# sub.net
KiCad netlist of a schematic drawn in EAGLE
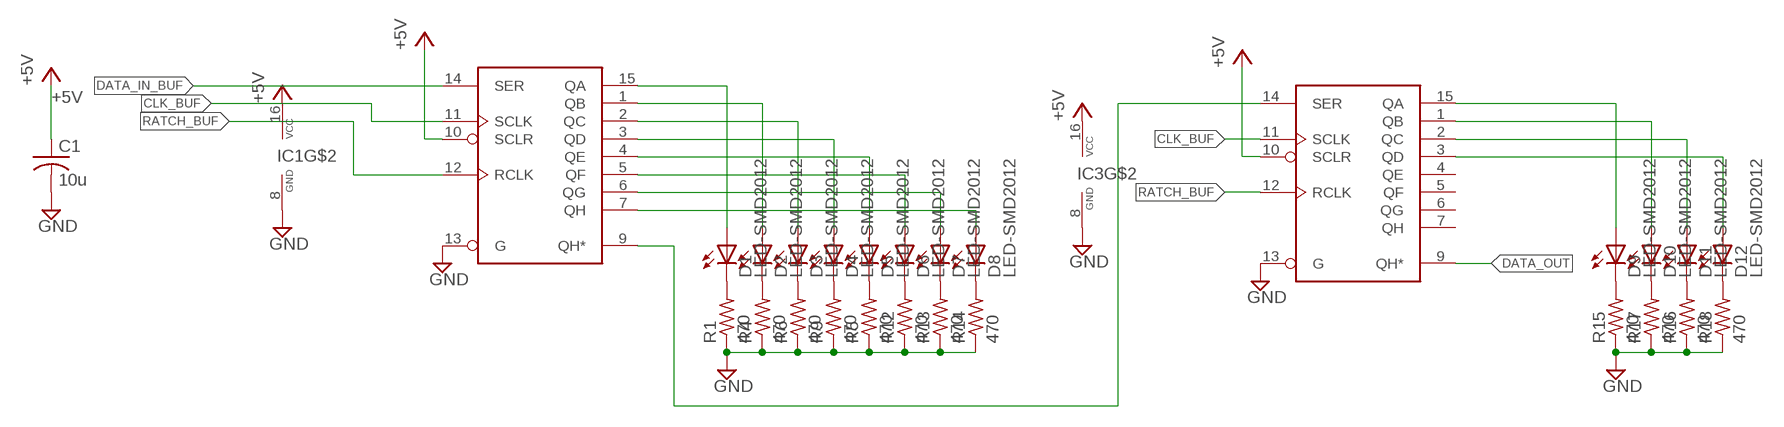
[diagram p0: schematic, sheet 1]

(export (version "E")
  (design (tool "Eeschema 10.0.6"))
  (components
    (comp (ref "C1")
      (value "10u")
      (footprint "eagle-import:2012-C")
      (libsource (lib "eagle-import") (part "C-2012"))
    )
    (comp (ref "D1")
      (value "LED-SMD2012")
      (footprint "eagle-import:D2012")
      (libsource (lib "eagle-import") (part "LED-SMD2012"))
    )
    (comp (ref "D2")
      (value "LED-SMD2012")
      (footprint "eagle-import:D2012")
      (libsource (lib "eagle-import") (part "LED-SMD2012"))
    )
    (comp (ref "D3")
      (value "LED-SMD2012")
      (footprint "eagle-import:D2012")
      (libsource (lib "eagle-import") (part "LED-SMD2012"))
    )
    (comp (ref "D4")
      (value "LED-SMD2012")
      (footprint "eagle-import:D2012")
      (libsource (lib "eagle-import") (part "LED-SMD2012"))
    )
    (comp (ref "D5")
      (value "LED-SMD2012")
      (footprint "eagle-import:D2012")
      (libsource (lib "eagle-import") (part "LED-SMD2012"))
    )
    (comp (ref "D6")
      (value "LED-SMD2012")
      (footprint "eagle-import:D2012")
      (libsource (lib "eagle-import") (part "LED-SMD2012"))
    )
    (comp (ref "D7")
      (value "LED-SMD2012")
      (footprint "eagle-import:D2012")
      (libsource (lib "eagle-import") (part "LED-SMD2012"))
    )
    (comp (ref "D8")
      (value "LED-SMD2012")
      (footprint "eagle-import:D2012")
      (libsource (lib "eagle-import") (part "LED-SMD2012"))
    )
    (comp (ref "D9")
      (value "LED-SMD2012")
      (footprint "eagle-import:D2012")
      (libsource (lib "eagle-import") (part "LED-SMD2012"))
    )
    (comp (ref "D10")
      (value "LED-SMD2012")
      (footprint "eagle-import:D2012")
      (libsource (lib "eagle-import") (part "LED-SMD2012"))
    )
    (comp (ref "D11")
      (value "LED-SMD2012")
      (footprint "eagle-import:D2012")
      (libsource (lib "eagle-import") (part "LED-SMD2012"))
    )
    (comp (ref "D12")
      (value "LED-SMD2012")
      (footprint "eagle-import:D2012")
      (libsource (lib "eagle-import") (part "LED-SMD2012"))
    )
    (comp (ref "IC1")
      (value "74595AP")
      (footprint "eagle-import:SOP16")
      (libsource (lib "eagle-import") (part "74595AP"))
    )
    (comp (ref "IC3")
      (value "74595AP")
      (footprint "eagle-import:SOP16")
      (libsource (lib "eagle-import") (part "74595AP"))
    )
    (comp (ref "R1")
      (value "470")
      (footprint "eagle-import:2012-R")
      (libsource (lib "eagle-import") (part "R-2012"))
    )
    (comp (ref "R4")
      (value "470")
      (footprint "eagle-import:2012-R")
      (libsource (lib "eagle-import") (part "R-2012"))
    )
    (comp (ref "R5")
      (value "470")
      (footprint "eagle-import:2012-R")
      (libsource (lib "eagle-import") (part "R-2012"))
    )
    (comp (ref "R6")
      (value "470")
      (footprint "eagle-import:2012-R")
      (libsource (lib "eagle-import") (part "R-2012"))
    )
    (comp (ref "R9")
      (value "470")
      (footprint "eagle-import:2012-R")
      (libsource (lib "eagle-import") (part "R-2012"))
    )
    (comp (ref "R12")
      (value "470")
      (footprint "eagle-import:2012-R")
      (libsource (lib "eagle-import") (part "R-2012"))
    )
    (comp (ref "R13")
      (value "470")
      (footprint "eagle-import:2012-R")
      (libsource (lib "eagle-import") (part "R-2012"))
    )
    (comp (ref "R14")
      (value "470")
      (footprint "eagle-import:2012-R")
      (libsource (lib "eagle-import") (part "R-2012"))
    )
    (comp (ref "R15")
      (value "470")
      (footprint "eagle-import:2012-R")
      (libsource (lib "eagle-import") (part "R-2012"))
    )
    (comp (ref "R16")
      (value "470")
      (footprint "eagle-import:2012-R")
      (libsource (lib "eagle-import") (part "R-2012"))
    )
    (comp (ref "R17")
      (value "470")
      (footprint "eagle-import:2012-R")
      (libsource (lib "eagle-import") (part "R-2012"))
    )
    (comp (ref "R18")
      (value "470")
      (footprint "eagle-import:2012-R")
      (libsource (lib "eagle-import") (part "R-2012"))
    )
  )
  (nets
    (net (code "1") (name "+5V") (class "Default")
      (node (ref "C1") (pin "1") (pinfunction "1_1") (pintype "passive"))
      (node (ref "IC1") (pin "10") (pinfunction "SCLR_10") (pintype "input"))
      (node (ref "IC1") (pin "16") (pinfunction "VCC_16") (pintype "power_in"))
      (node (ref "IC3") (pin "10") (pinfunction "SCLR_10") (pintype "input"))
      (node (ref "IC3") (pin "16") (pinfunction "VCC_16") (pintype "power_in"))
    )
    (net (code "2") (name "CLK_BUF") (class "Default")
      (node (ref "IC1") (pin "11") (pinfunction "SCLK_11") (pintype "input"))
      (node (ref "IC3") (pin "11") (pinfunction "SCLK_11") (pintype "input"))
    )
    (net (code "3") (name "DATA_IN_BUF") (class "Default")
      (node (ref "IC1") (pin "14") (pinfunction "SER_14") (pintype "input"))
    )
    (net (code "4") (name "DATA_OUT") (class "Default")
      (node (ref "IC3") (pin "9") (pinfunction "QH*_9") (pintype "output"))
    )
    (net (code "5") (name "GND") (class "Default")
      (node (ref "C1") (pin "2") (pinfunction "2_2") (pintype "passive"))
      (node (ref "IC1") (pin "13") (pinfunction "G_13") (pintype "input"))
      (node (ref "IC1") (pin "8") (pinfunction "GND_8") (pintype "power_in"))
      (node (ref "IC3") (pin "13") (pinfunction "G_13") (pintype "input"))
      (node (ref "IC3") (pin "8") (pinfunction "GND_8") (pintype "power_in"))
      (node (ref "R1") (pin "1") (pinfunction "1_1") (pintype "passive"))
      (node (ref "R12") (pin "1") (pinfunction "1_1") (pintype "passive"))
      (node (ref "R13") (pin "1") (pinfunction "1_1") (pintype "passive"))
      (node (ref "R14") (pin "1") (pinfunction "1_1") (pintype "passive"))
      (node (ref "R15") (pin "1") (pinfunction "1_1") (pintype "passive"))
      (node (ref "R16") (pin "1") (pinfunction "1_1") (pintype "passive"))
      (node (ref "R17") (pin "1") (pinfunction "1_1") (pintype "passive"))
      (node (ref "R18") (pin "1") (pinfunction "1_1") (pintype "passive"))
      (node (ref "R4") (pin "1") (pinfunction "1_1") (pintype "passive"))
      (node (ref "R5") (pin "1") (pinfunction "1_1") (pintype "passive"))
      (node (ref "R6") (pin "1") (pinfunction "1_1") (pintype "passive"))
      (node (ref "R9") (pin "1") (pinfunction "1_1") (pintype "passive"))
    )
    (net (code "6") (name "Net-(D1-PadK)") (class "Default")
      (node (ref "D1") (pin "K") (pinfunction "K_K") (pintype "passive"))
      (node (ref "R1") (pin "2") (pinfunction "2_2") (pintype "passive"))
    )
    (net (code "7") (name "Net-(D2-PadK)") (class "Default")
      (node (ref "D2") (pin "K") (pinfunction "K_K") (pintype "passive"))
      (node (ref "R4") (pin "2") (pinfunction "2_2") (pintype "passive"))
    )
    (net (code "8") (name "Net-(D3-PadK)") (class "Default")
      (node (ref "D3") (pin "K") (pinfunction "K_K") (pintype "passive"))
      (node (ref "R6") (pin "2") (pinfunction "2_2") (pintype "passive"))
    )
    (net (code "9") (name "Net-(D4-PadK)") (class "Default")
      (node (ref "D4") (pin "K") (pinfunction "K_K") (pintype "passive"))
      (node (ref "R9") (pin "2") (pinfunction "2_2") (pintype "passive"))
    )
    (net (code "10") (name "Net-(D5-PadK)") (class "Default")
      (node (ref "D5") (pin "K") (pinfunction "K_K") (pintype "passive"))
      (node (ref "R5") (pin "2") (pinfunction "2_2") (pintype "passive"))
    )
    (net (code "11") (name "Net-(D6-PadK)") (class "Default")
      (node (ref "D6") (pin "K") (pinfunction "K_K") (pintype "passive"))
      (node (ref "R12") (pin "2") (pinfunction "2_2") (pintype "passive"))
    )
    (net (code "12") (name "Net-(D7-PadK)") (class "Default")
      (node (ref "D7") (pin "K") (pinfunction "K_K") (pintype "passive"))
      (node (ref "R13") (pin "2") (pinfunction "2_2") (pintype "passive"))
    )
    (net (code "13") (name "Net-(D8-PadK)") (class "Default")
      (node (ref "D8") (pin "K") (pinfunction "K_K") (pintype "passive"))
      (node (ref "R14") (pin "2") (pinfunction "2_2") (pintype "passive"))
    )
    (net (code "14") (name "Net-(D9-PadK)") (class "Default")
      (node (ref "D9") (pin "K") (pinfunction "K_K") (pintype "passive"))
      (node (ref "R15") (pin "2") (pinfunction "2_2") (pintype "passive"))
    )
    (net (code "15") (name "Net-(D10-PadK)") (class "Default")
      (node (ref "D10") (pin "K") (pinfunction "K_K") (pintype "passive"))
      (node (ref "R17") (pin "2") (pinfunction "2_2") (pintype "passive"))
    )
    (net (code "16") (name "Net-(D11-PadK)") (class "Default")
      (node (ref "D11") (pin "K") (pinfunction "K_K") (pintype "passive"))
      (node (ref "R16") (pin "2") (pinfunction "2_2") (pintype "passive"))
    )
    (net (code "17") (name "Net-(D12-PadK)") (class "Default")
      (node (ref "D12") (pin "K") (pinfunction "K_K") (pintype "passive"))
      (node (ref "R18") (pin "2") (pinfunction "2_2") (pintype "passive"))
    )
    (net (code "18") (name "Net-(IC1A-QA)") (class "Default")
      (node (ref "D1") (pin "A") (pinfunction "A_A") (pintype "passive"))
      (node (ref "IC1") (pin "15") (pinfunction "QA_15") (pintype "output"))
    )
    (net (code "19") (name "Net-(IC1A-QB)") (class "Default")
      (node (ref "D2") (pin "A") (pinfunction "A_A") (pintype "passive"))
      (node (ref "IC1") (pin "1") (pinfunction "QB_1") (pintype "output"))
    )
    (net (code "20") (name "Net-(IC1A-QC)") (class "Default")
      (node (ref "D3") (pin "A") (pinfunction "A_A") (pintype "passive"))
      (node (ref "IC1") (pin "2") (pinfunction "QC_2") (pintype "output"))
    )
    (net (code "21") (name "Net-(IC1A-QD)") (class "Default")
      (node (ref "D4") (pin "A") (pinfunction "A_A") (pintype "passive"))
      (node (ref "IC1") (pin "3") (pinfunction "QD_3") (pintype "output"))
    )
    (net (code "22") (name "Net-(IC1A-QE)") (class "Default")
      (node (ref "D5") (pin "A") (pinfunction "A_A") (pintype "passive"))
      (node (ref "IC1") (pin "4") (pinfunction "QE_4") (pintype "output"))
    )
    (net (code "23") (name "Net-(IC1A-QF)") (class "Default")
      (node (ref "D6") (pin "A") (pinfunction "A_A") (pintype "passive"))
      (node (ref "IC1") (pin "5") (pinfunction "QF_5") (pintype "output"))
    )
    (net (code "24") (name "Net-(IC1A-QG)") (class "Default")
      (node (ref "D7") (pin "A") (pinfunction "A_A") (pintype "passive"))
      (node (ref "IC1") (pin "6") (pinfunction "QG_6") (pintype "output"))
    )
    (net (code "25") (name "Net-(IC1A-QH)") (class "Default")
      (node (ref "D8") (pin "A") (pinfunction "A_A") (pintype "passive"))
      (node (ref "IC1") (pin "7") (pinfunction "QH_7") (pintype "output"))
    )
    (net (code "26") (name "Net-(IC1A-QH*)") (class "Default")
      (node (ref "IC1") (pin "9") (pinfunction "QH*_9") (pintype "output"))
      (node (ref "IC3") (pin "14") (pinfunction "SER_14") (pintype "input"))
    )
    (net (code "27") (name "Net-(IC3A-QA)") (class "Default")
      (node (ref "D9") (pin "A") (pinfunction "A_A") (pintype "passive"))
      (node (ref "IC3") (pin "15") (pinfunction "QA_15") (pintype "output"))
    )
    (net (code "28") (name "Net-(IC3A-QB)") (class "Default")
      (node (ref "D10") (pin "A") (pinfunction "A_A") (pintype "passive"))
      (node (ref "IC3") (pin "1") (pinfunction "QB_1") (pintype "output"))
    )
    (net (code "29") (name "Net-(IC3A-QC)") (class "Default")
      (node (ref "D11") (pin "A") (pinfunction "A_A") (pintype "passive"))
      (node (ref "IC3") (pin "2") (pinfunction "QC_2") (pintype "output"))
    )
    (net (code "30") (name "Net-(IC3A-QD)") (class "Default")
      (node (ref "D12") (pin "A") (pinfunction "A_A") (pintype "passive"))
      (node (ref "IC3") (pin "3") (pinfunction "QD_3") (pintype "output"))
    )
    (net (code "31") (name "RATCH_BUF") (class "Default")
      (node (ref "IC1") (pin "12") (pinfunction "RCLK_12") (pintype "input"))
      (node (ref "IC3") (pin "12") (pinfunction "RCLK_12") (pintype "input"))
    )
    (net (code "32") (name "unconnected-(IC3A-QE-Pad4)") (class "Default")
      (node (ref "IC3") (pin "4") (pinfunction "QE_4") (pintype "output"))
    )
    (net (code "33") (name "unconnected-(IC3A-QF-Pad5)") (class "Default")
      (node (ref "IC3") (pin "5") (pinfunction "QF_5") (pintype "output"))
    )
    (net (code "34") (name "unconnected-(IC3A-QG-Pad6)") (class "Default")
      (node (ref "IC3") (pin "6") (pinfunction "QG_6") (pintype "output"))
    )
    (net (code "35") (name "unconnected-(IC3A-QH-Pad7)") (class "Default")
      (node (ref "IC3") (pin "7") (pinfunction "QH_7") (pintype "output"))
    )
  )
)
